# P07_Hi3531AV100_POWER.net
KiCad netlist of a schematic drawn in Altium Designer
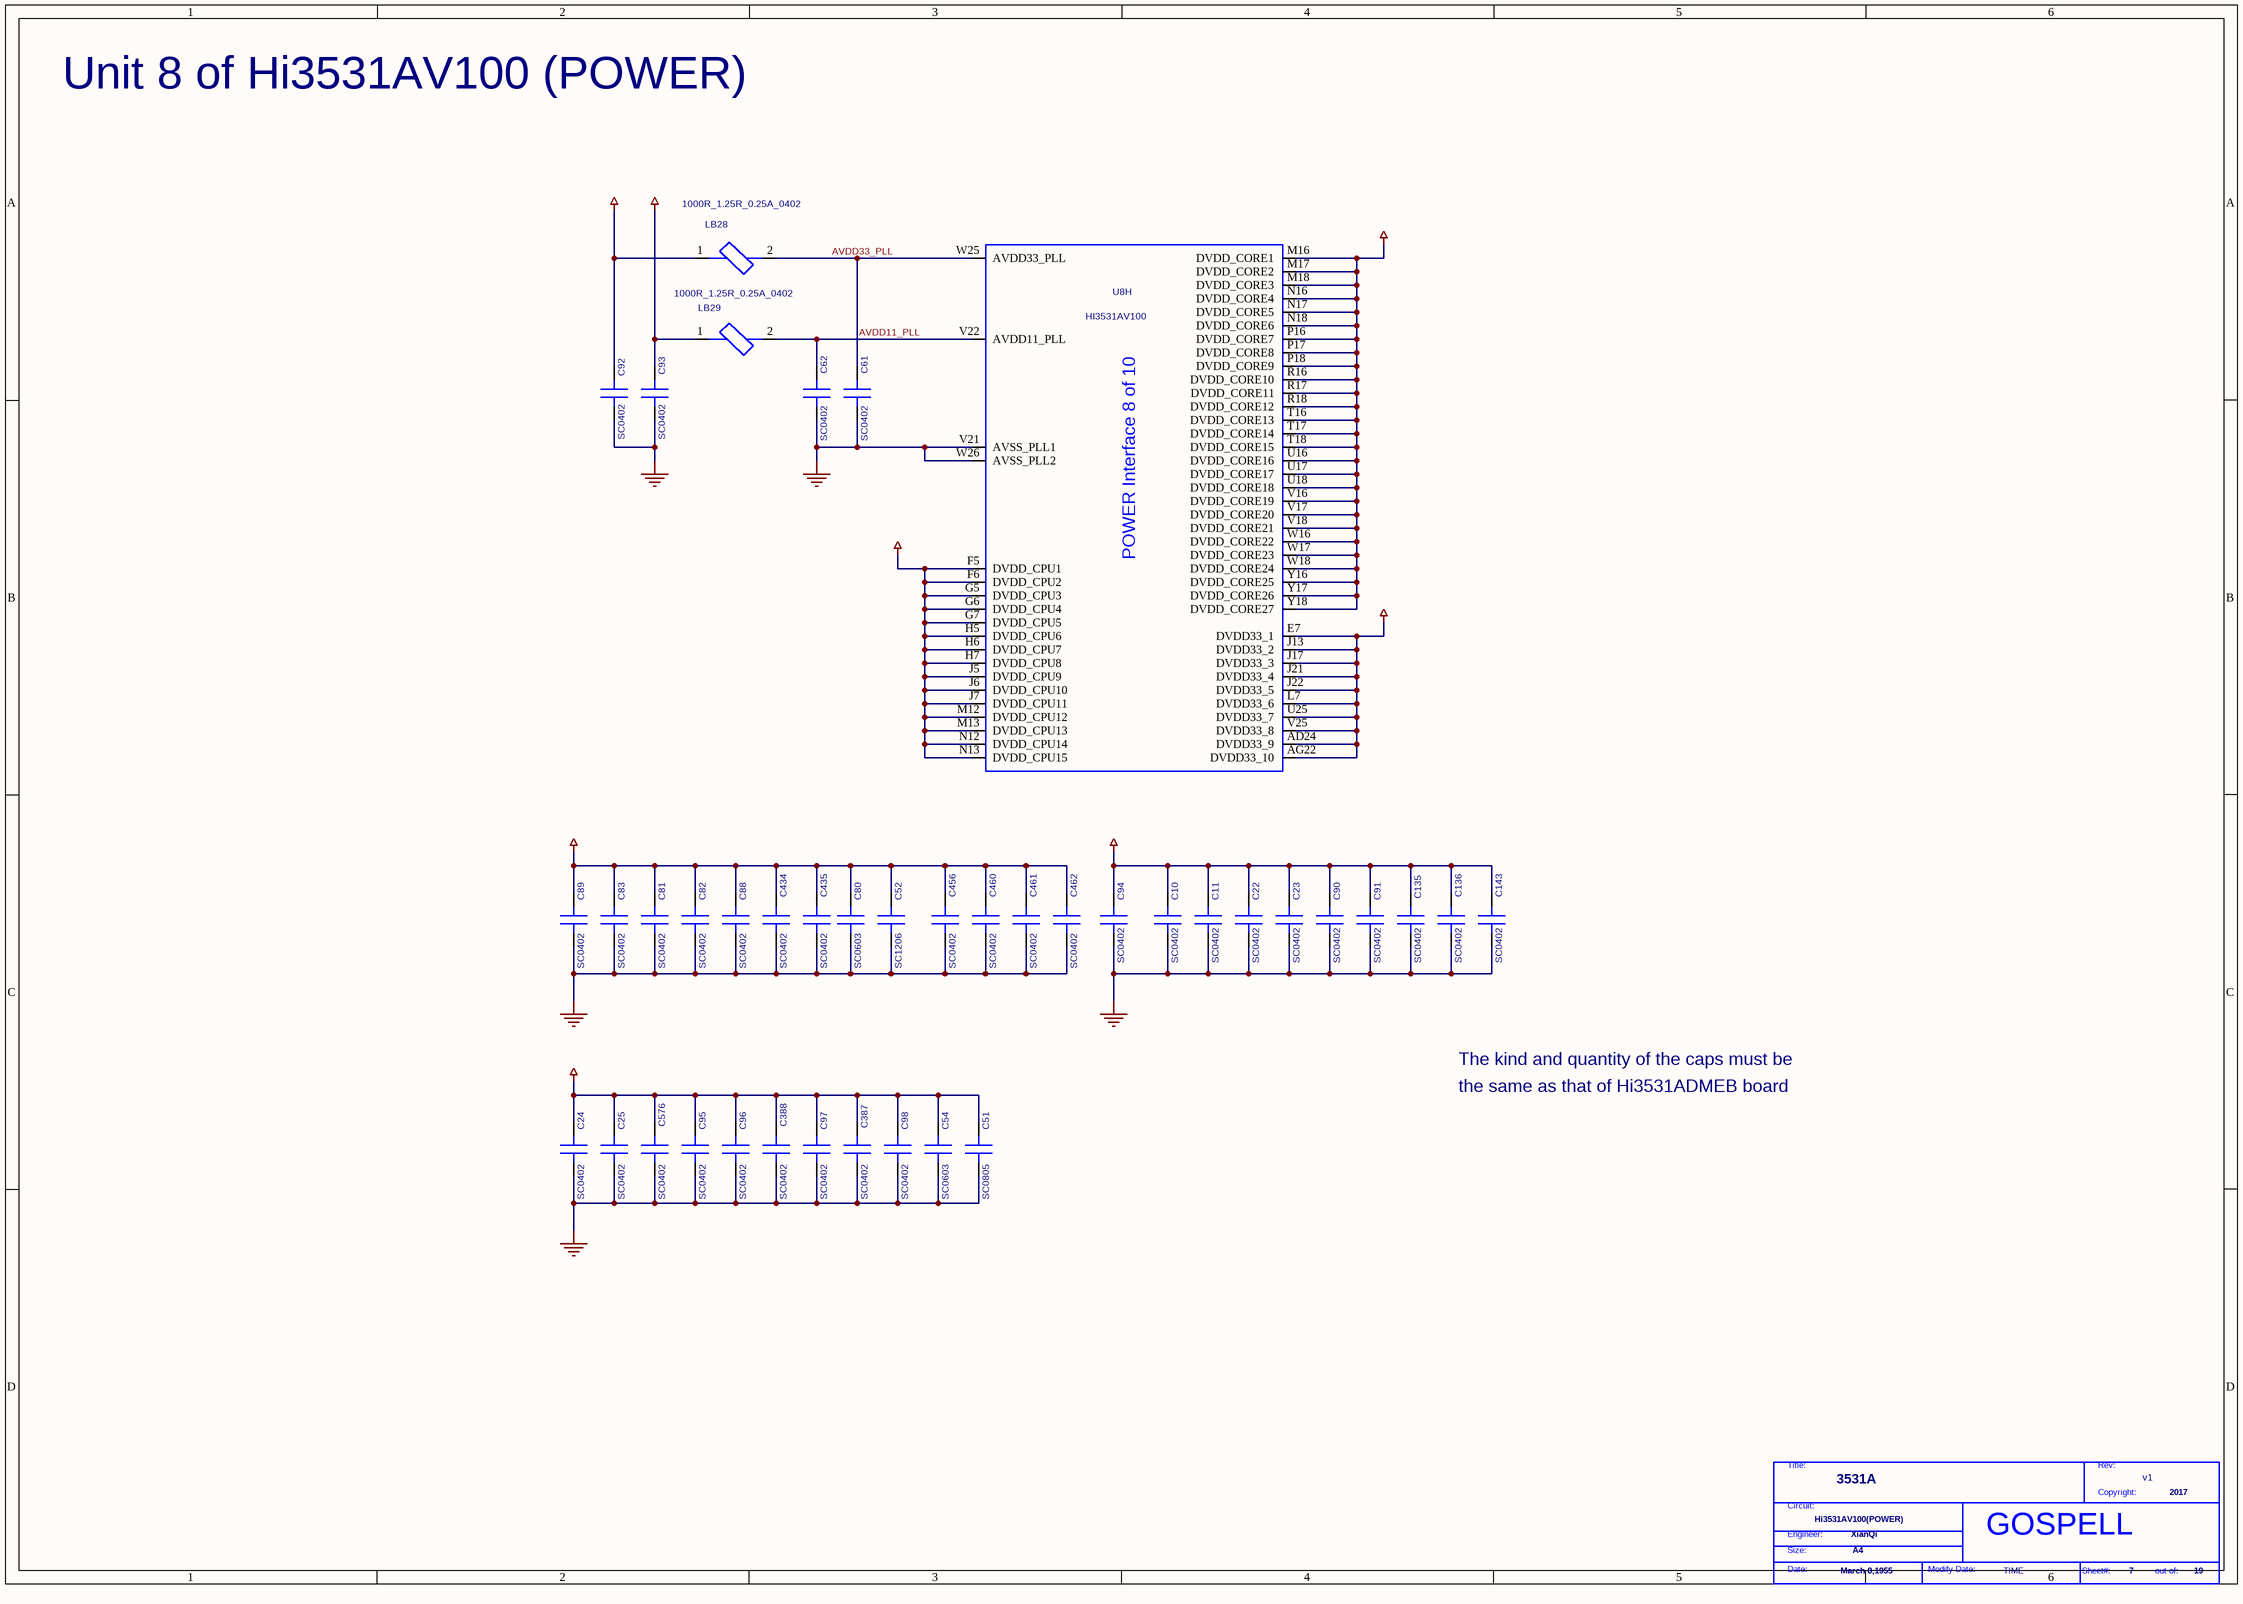
[diagram p0: P07 Hi3531AV100(POWER).SchDoc]

(export (version "E")
  (design (tool "Eeschema 10.0.6"))
  (components
    (comp (ref "C10") (value "SC0402") (libsource (lib "*") (part "C_0_Dup2")))
    (comp (ref "C11") (value "SC0402") (libsource (lib "*") (part "C_0_Dup2")))
    (comp (ref "C22") (value "SC0402") (libsource (lib "*") (part "C_0_Dup2")))
    (comp (ref "C23") (value "SC0402") (libsource (lib "*") (part "C_0_Dup2")))
    (comp (ref "C24") (value "SC0402") (libsource (lib "*") (part "C_0_Dup2")))
    (comp (ref "C25") (value "SC0402") (libsource (lib "*") (part "C_0_Dup2")))
    (comp (ref "C51") (value "SC0805") (libsource (lib "*") (part "C_0_Dup2")))
    (comp (ref "C52") (value "SC1206") (libsource (lib "*") (part "C_0_Dup2")))
    (comp (ref "C54") (value "SC0603") (libsource (lib "*") (part "C_0_Dup2")))
    (comp (ref "C61") (value "SC0402") (libsource (lib "*") (part "C_0_Dup2")))
    (comp (ref "C62") (value "SC0402") (libsource (lib "*") (part "C_0_Dup2")))
    (comp (ref "C80") (value "SC0603") (libsource (lib "*") (part "C_0_Dup2")))
    (comp (ref "C81") (value "SC0402") (libsource (lib "*") (part "C_0_Dup2")))
    (comp (ref "C82") (value "SC0402") (libsource (lib "*") (part "C_0_Dup2")))
    (comp (ref "C83") (value "SC0402") (libsource (lib "*") (part "C_0_Dup2")))
    (comp (ref "C88") (value "SC0402") (libsource (lib "*") (part "C_0_Dup2")))
    (comp (ref "C89") (value "SC0402") (libsource (lib "*") (part "C_0_Dup2")))
    (comp (ref "C90") (value "SC0402") (libsource (lib "*") (part "C_0_Dup2")))
    (comp (ref "C91") (value "SC0402") (libsource (lib "*") (part "C_0_Dup2")))
    (comp (ref "C92") (value "SC0402") (libsource (lib "*") (part "C_0_Dup2")))
    (comp (ref "C93") (value "SC0402") (libsource (lib "*") (part "C_0_Dup2")))
    (comp (ref "C94") (value "SC0402") (libsource (lib "*") (part "C_0_Dup2")))
    (comp (ref "C95") (value "SC0402") (libsource (lib "*") (part "C_0_Dup2")))
    (comp (ref "C96") (value "SC0402") (libsource (lib "*") (part "C_0_Dup2")))
    (comp (ref "C97") (value "SC0402") (libsource (lib "*") (part "C_0_Dup2")))
    (comp (ref "C98") (value "SC0402") (libsource (lib "*") (part "C_0_Dup2")))
    (comp (ref "C135") (value "SC0402") (libsource (lib "*") (part "C_0_Dup2")))
    (comp (ref "C136") (value "SC0402") (libsource (lib "*") (part "C_0_Dup2")))
    (comp (ref "C143") (value "SC0402") (libsource (lib "*") (part "C_0_Dup2")))
    (comp (ref "C387") (value "SC0402") (libsource (lib "*") (part "C_0_Dup2")))
    (comp (ref "C388") (value "SC0402") (libsource (lib "*") (part "C_0_Dup2")))
    (comp (ref "C434") (value "SC0402") (libsource (lib "*") (part "C_0_Dup2")))
    (comp (ref "C435") (value "SC0402") (libsource (lib "*") (part "C_0_Dup2")))
    (comp (ref "C456") (value "SC0402") (libsource (lib "*") (part "C_0_Dup2")))
    (comp (ref "C460") (value "SC0402") (libsource (lib "*") (part "C_0_Dup2")))
    (comp (ref "C461") (value "SC0402") (libsource (lib "*") (part "C_0_Dup2")))
    (comp (ref "C462") (value "SC0402") (libsource (lib "*") (part "C_0_Dup2")))
    (comp (ref "C576") (value "SC0402") (libsource (lib "*") (part "C_0_Dup2")))
    (comp (ref "LB28") (value "SL0402") (libsource (lib "*") (part "LB_0")))
    (comp (ref "LB29") (value "SL0402") (libsource (lib "*") (part "LB_0")))
    (comp (ref "U8")
      (value "BGA805-32-3333")
      (fields (field (name "DEVICE") "HI3531AV100"))
      (libsource (lib "*") (part "HI3531AV100_M2_17"))
    )
  )
  (nets
    (net (code "1") (name "/AVDD11_PLL") (class "Default")
      (node (ref "C62") (pin "1") (pinfunction "A_1") (pintype "passive"))
      (node (ref "LB29") (pin "2") (pinfunction "2_2") (pintype "passive"))
      (node (ref "U8") (pin "V22") (pinfunction "AVDD11_PLL_V22") (pintype "passive"))
    )
    (net (code "2") (name "/AVDD33_PLL") (class "Default")
      (node (ref "C61") (pin "1") (pinfunction "A_1") (pintype "passive"))
      (node (ref "LB28") (pin "2") (pinfunction "2_2") (pintype "passive"))
      (node (ref "U8") (pin "W25") (pinfunction "AVDD33_PLL_W25") (pintype "passive"))
    )
    (net (code "3") (name "3V3") (class "Default")
      (node (ref "C10") (pin "1") (pinfunction "A_1") (pintype "passive"))
      (node (ref "C11") (pin "1") (pinfunction "A_1") (pintype "passive"))
      (node (ref "C135") (pin "1") (pinfunction "A_1") (pintype "passive"))
      (node (ref "C136") (pin "1") (pinfunction "A_1") (pintype "passive"))
      (node (ref "C143") (pin "1") (pinfunction "A_1") (pintype "passive"))
      (node (ref "C22") (pin "1") (pinfunction "A_1") (pintype "passive"))
      (node (ref "C23") (pin "1") (pinfunction "A_1") (pintype "passive"))
      (node (ref "C90") (pin "1") (pinfunction "A_1") (pintype "passive"))
      (node (ref "C91") (pin "1") (pinfunction "A_1") (pintype "passive"))
      (node (ref "C92") (pin "1") (pinfunction "A_1") (pintype "passive"))
      (node (ref "C94") (pin "1") (pinfunction "A_1") (pintype "passive"))
      (node (ref "LB28") (pin "1") (pinfunction "1_1") (pintype "passive"))
      (node (ref "U8") (pin "AD24") (pinfunction "DVDD33_9_AD24") (pintype "passive"))
      (node (ref "U8") (pin "AG22") (pinfunction "DVDD33_10_AG22") (pintype "passive"))
      (node (ref "U8") (pin "E7") (pinfunction "DVDD33_1_E7") (pintype "passive"))
      (node (ref "U8") (pin "J13") (pinfunction "DVDD33_2_J13") (pintype "passive"))
      (node (ref "U8") (pin "J17") (pinfunction "DVDD33_3_J17") (pintype "passive"))
      (node (ref "U8") (pin "J21") (pinfunction "DVDD33_4_J21") (pintype "passive"))
      (node (ref "U8") (pin "J22") (pinfunction "DVDD33_5_J22") (pintype "passive"))
      (node (ref "U8") (pin "L7") (pinfunction "DVDD33_6_L7") (pintype "passive"))
      (node (ref "U8") (pin "U25") (pinfunction "DVDD33_7_U25") (pintype "passive"))
      (node (ref "U8") (pin "V25") (pinfunction "DVDD33_8_V25") (pintype "passive"))
    )
    (net (code "4") (name "DVDD_CORE") (class "Default")
      (node (ref "C24") (pin "1") (pinfunction "A_1") (pintype "passive"))
      (node (ref "C25") (pin "1") (pinfunction "A_1") (pintype "passive"))
      (node (ref "C387") (pin "1") (pinfunction "A_1") (pintype "passive"))
      (node (ref "C388") (pin "1") (pinfunction "A_1") (pintype "passive"))
      (node (ref "C51") (pin "1") (pinfunction "A_1") (pintype "passive"))
      (node (ref "C54") (pin "1") (pinfunction "A_1") (pintype "passive"))
      (node (ref "C576") (pin "1") (pinfunction "A_1") (pintype "passive"))
      (node (ref "C93") (pin "1") (pinfunction "A_1") (pintype "passive"))
      (node (ref "C95") (pin "1") (pinfunction "A_1") (pintype "passive"))
      (node (ref "C96") (pin "1") (pinfunction "A_1") (pintype "passive"))
      (node (ref "C97") (pin "1") (pinfunction "A_1") (pintype "passive"))
      (node (ref "C98") (pin "1") (pinfunction "A_1") (pintype "passive"))
      (node (ref "LB29") (pin "1") (pinfunction "1_1") (pintype "passive"))
      (node (ref "U8") (pin "M16") (pinfunction "DVDD_CORE1_M16") (pintype "passive"))
      (node (ref "U8") (pin "M17") (pinfunction "DVDD_CORE2_M17") (pintype "passive"))
      (node (ref "U8") (pin "M18") (pinfunction "DVDD_CORE3_M18") (pintype "passive"))
      (node (ref "U8") (pin "N16") (pinfunction "DVDD_CORE4_N16") (pintype "passive"))
      (node (ref "U8") (pin "N17") (pinfunction "DVDD_CORE5_N17") (pintype "passive"))
      (node (ref "U8") (pin "N18") (pinfunction "DVDD_CORE6_N18") (pintype "passive"))
      (node (ref "U8") (pin "P16") (pinfunction "DVDD_CORE7_P16") (pintype "passive"))
      (node (ref "U8") (pin "P17") (pinfunction "DVDD_CORE8_P17") (pintype "passive"))
      (node (ref "U8") (pin "P18") (pinfunction "DVDD_CORE9_P18") (pintype "passive"))
      (node (ref "U8") (pin "R16") (pinfunction "DVDD_CORE10_R16") (pintype "passive"))
      (node (ref "U8") (pin "R17") (pinfunction "DVDD_CORE11_R17") (pintype "passive"))
      (node (ref "U8") (pin "R18") (pinfunction "DVDD_CORE12_R18") (pintype "passive"))
      (node (ref "U8") (pin "T16") (pinfunction "DVDD_CORE13_T16") (pintype "passive"))
      (node (ref "U8") (pin "T17") (pinfunction "DVDD_CORE14_T17") (pintype "passive"))
      (node (ref "U8") (pin "T18") (pinfunction "DVDD_CORE15_T18") (pintype "passive"))
      (node (ref "U8") (pin "U16") (pinfunction "DVDD_CORE16_U16") (pintype "passive"))
      (node (ref "U8") (pin "U17") (pinfunction "DVDD_CORE17_U17") (pintype "passive"))
      (node (ref "U8") (pin "U18") (pinfunction "DVDD_CORE18_U18") (pintype "passive"))
      (node (ref "U8") (pin "V16") (pinfunction "DVDD_CORE19_V16") (pintype "passive"))
      (node (ref "U8") (pin "V17") (pinfunction "DVDD_CORE20_V17") (pintype "passive"))
      (node (ref "U8") (pin "V18") (pinfunction "DVDD_CORE21_V18") (pintype "passive"))
      (node (ref "U8") (pin "W16") (pinfunction "DVDD_CORE22_W16") (pintype "passive"))
      (node (ref "U8") (pin "W17") (pinfunction "DVDD_CORE23_W17") (pintype "passive"))
      (node (ref "U8") (pin "W18") (pinfunction "DVDD_CORE24_W18") (pintype "passive"))
      (node (ref "U8") (pin "Y16") (pinfunction "DVDD_CORE25_Y16") (pintype "passive"))
      (node (ref "U8") (pin "Y17") (pinfunction "DVDD_CORE26_Y17") (pintype "passive"))
      (node (ref "U8") (pin "Y18") (pinfunction "DVDD_CORE27_Y18") (pintype "passive"))
    )
    (net (code "5") (name "DVDD_CPU") (class "Default")
      (node (ref "C434") (pin "1") (pinfunction "A_1") (pintype "passive"))
      (node (ref "C435") (pin "1") (pinfunction "A_1") (pintype "passive"))
      (node (ref "C456") (pin "1") (pinfunction "A_1") (pintype "passive"))
      (node (ref "C460") (pin "1") (pinfunction "A_1") (pintype "passive"))
      (node (ref "C461") (pin "1") (pinfunction "A_1") (pintype "passive"))
      (node (ref "C462") (pin "1") (pinfunction "A_1") (pintype "passive"))
      (node (ref "C52") (pin "1") (pinfunction "A_1") (pintype "passive"))
      (node (ref "C80") (pin "1") (pinfunction "A_1") (pintype "passive"))
      (node (ref "C81") (pin "1") (pinfunction "A_1") (pintype "passive"))
      (node (ref "C82") (pin "1") (pinfunction "A_1") (pintype "passive"))
      (node (ref "C83") (pin "1") (pinfunction "A_1") (pintype "passive"))
      (node (ref "C88") (pin "1") (pinfunction "A_1") (pintype "passive"))
      (node (ref "C89") (pin "1") (pinfunction "A_1") (pintype "passive"))
      (node (ref "U8") (pin "F5") (pinfunction "DVDD_CPU1_F5") (pintype "passive"))
      (node (ref "U8") (pin "F6") (pinfunction "DVDD_CPU2_F6") (pintype "passive"))
      (node (ref "U8") (pin "G5") (pinfunction "DVDD_CPU3_G5") (pintype "passive"))
      (node (ref "U8") (pin "G6") (pinfunction "DVDD_CPU4_G6") (pintype "passive"))
      (node (ref "U8") (pin "G7") (pinfunction "DVDD_CPU5_G7") (pintype "passive"))
      (node (ref "U8") (pin "H5") (pinfunction "DVDD_CPU6_H5") (pintype "passive"))
      (node (ref "U8") (pin "H6") (pinfunction "DVDD_CPU7_H6") (pintype "passive"))
      (node (ref "U8") (pin "H7") (pinfunction "DVDD_CPU8_H7") (pintype "passive"))
      (node (ref "U8") (pin "J5") (pinfunction "DVDD_CPU9_J5") (pintype "passive"))
      (node (ref "U8") (pin "J6") (pinfunction "DVDD_CPU10_J6") (pintype "passive"))
      (node (ref "U8") (pin "J7") (pinfunction "DVDD_CPU11_J7") (pintype "passive"))
      (node (ref "U8") (pin "M12") (pinfunction "DVDD_CPU12_M12") (pintype "passive"))
      (node (ref "U8") (pin "M13") (pinfunction "DVDD_CPU13_M13") (pintype "passive"))
      (node (ref "U8") (pin "N12") (pinfunction "DVDD_CPU14_N12") (pintype "passive"))
      (node (ref "U8") (pin "N13") (pinfunction "DVDD_CPU15_N13") (pintype "passive"))
    )
    (net (code "6") (name "GND") (class "Default")
      (node (ref "C10") (pin "2") (pinfunction "B_2") (pintype "passive"))
      (node (ref "C11") (pin "2") (pinfunction "B_2") (pintype "passive"))
      (node (ref "C135") (pin "2") (pinfunction "B_2") (pintype "passive"))
      (node (ref "C136") (pin "2") (pinfunction "B_2") (pintype "passive"))
      (node (ref "C143") (pin "2") (pinfunction "B_2") (pintype "passive"))
      (node (ref "C22") (pin "2") (pinfunction "B_2") (pintype "passive"))
      (node (ref "C23") (pin "2") (pinfunction "B_2") (pintype "passive"))
      (node (ref "C24") (pin "2") (pinfunction "B_2") (pintype "passive"))
      (node (ref "C25") (pin "2") (pinfunction "B_2") (pintype "passive"))
      (node (ref "C387") (pin "2") (pinfunction "B_2") (pintype "passive"))
      (node (ref "C388") (pin "2") (pinfunction "B_2") (pintype "passive"))
      (node (ref "C434") (pin "2") (pinfunction "B_2") (pintype "passive"))
      (node (ref "C435") (pin "2") (pinfunction "B_2") (pintype "passive"))
      (node (ref "C456") (pin "2") (pinfunction "B_2") (pintype "passive"))
      (node (ref "C460") (pin "2") (pinfunction "B_2") (pintype "passive"))
      (node (ref "C461") (pin "2") (pinfunction "B_2") (pintype "passive"))
      (node (ref "C462") (pin "2") (pinfunction "B_2") (pintype "passive"))
      (node (ref "C51") (pin "2") (pinfunction "B_2") (pintype "passive"))
      (node (ref "C52") (pin "2") (pinfunction "B_2") (pintype "passive"))
      (node (ref "C54") (pin "2") (pinfunction "B_2") (pintype "passive"))
      (node (ref "C576") (pin "2") (pinfunction "B_2") (pintype "passive"))
      (node (ref "C61") (pin "2") (pinfunction "B_2") (pintype "passive"))
      (node (ref "C62") (pin "2") (pinfunction "B_2") (pintype "passive"))
      (node (ref "C80") (pin "2") (pinfunction "B_2") (pintype "passive"))
      (node (ref "C81") (pin "2") (pinfunction "B_2") (pintype "passive"))
      (node (ref "C82") (pin "2") (pinfunction "B_2") (pintype "passive"))
      (node (ref "C83") (pin "2") (pinfunction "B_2") (pintype "passive"))
      (node (ref "C88") (pin "2") (pinfunction "B_2") (pintype "passive"))
      (node (ref "C89") (pin "2") (pinfunction "B_2") (pintype "passive"))
      (node (ref "C90") (pin "2") (pinfunction "B_2") (pintype "passive"))
      (node (ref "C91") (pin "2") (pinfunction "B_2") (pintype "passive"))
      (node (ref "C92") (pin "2") (pinfunction "B_2") (pintype "passive"))
      (node (ref "C93") (pin "2") (pinfunction "B_2") (pintype "passive"))
      (node (ref "C94") (pin "2") (pinfunction "B_2") (pintype "passive"))
      (node (ref "C95") (pin "2") (pinfunction "B_2") (pintype "passive"))
      (node (ref "C96") (pin "2") (pinfunction "B_2") (pintype "passive"))
      (node (ref "C97") (pin "2") (pinfunction "B_2") (pintype "passive"))
      (node (ref "C98") (pin "2") (pinfunction "B_2") (pintype "passive"))
      (node (ref "U8") (pin "V21") (pinfunction "AVSS_PLL1_V21") (pintype "passive"))
      (node (ref "U8") (pin "W26") (pinfunction "AVSS_PLL2_W26") (pintype "passive"))
    )
  )
)
